# higheTemp.net
KiCad netlist of a schematic drawn in EAGLE
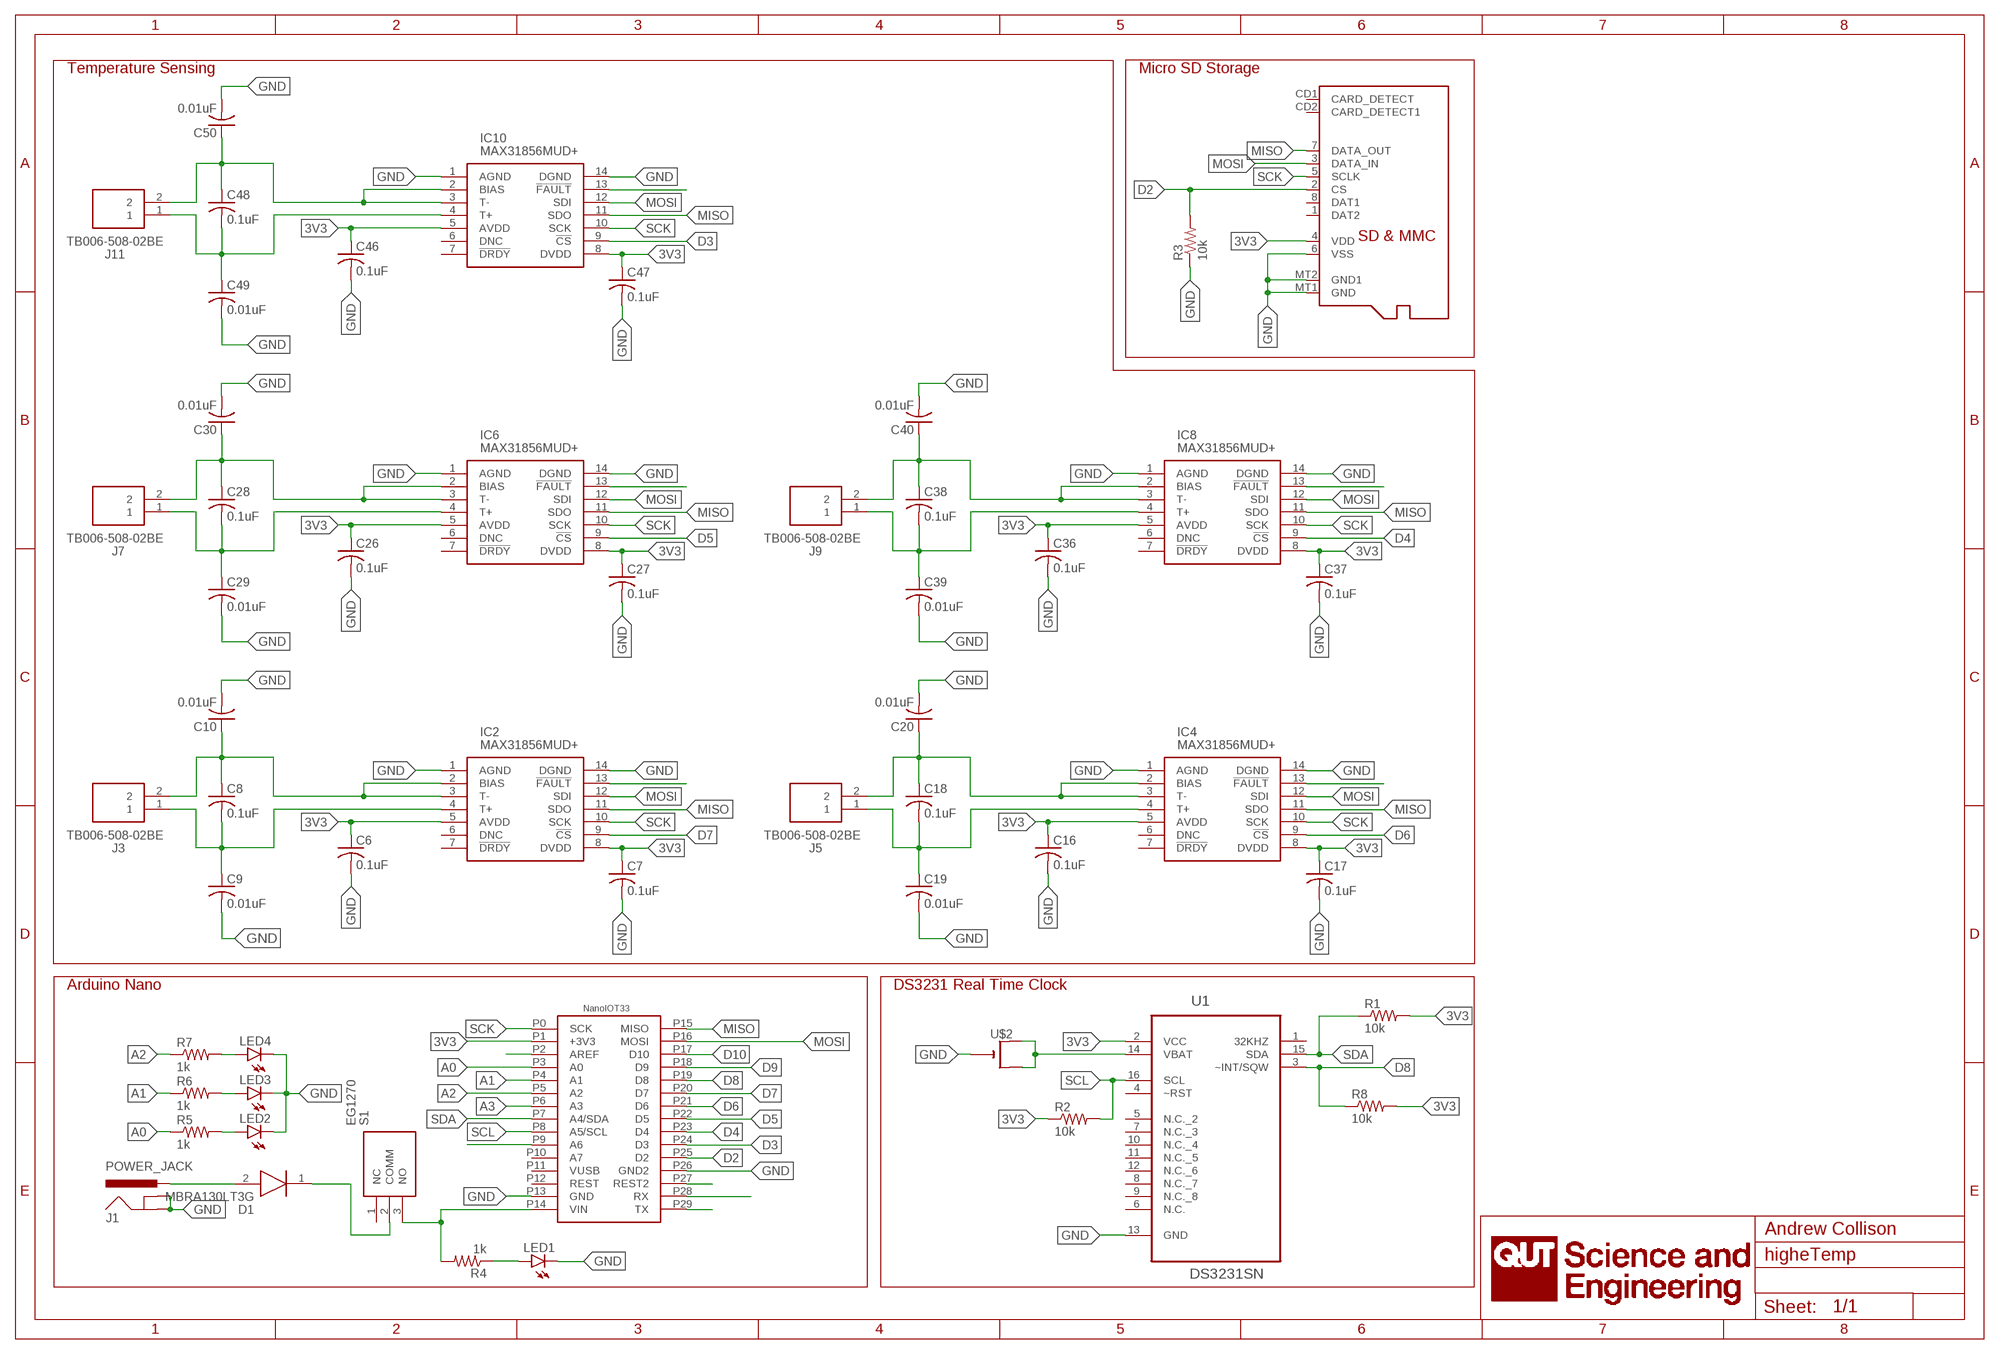
[diagram p0: schematic, sheet 1]

(export (version "E")
  (design (tool "Eeschema 10.0.6"))
  (components
    (comp (ref "C6")
      (value "0.1uF")
      (footprint "eagle-import:C0603")
      (libsource (lib "eagle-import") (part "C-USC0603"))
    )
    (comp (ref "C7")
      (value "0.1uF")
      (footprint "eagle-import:C0603")
      (libsource (lib "eagle-import") (part "C-USC0603"))
    )
    (comp (ref "C8")
      (value "0.1uF")
      (footprint "eagle-import:C0603")
      (libsource (lib "eagle-import") (part "C-USC0603"))
    )
    (comp (ref "C9")
      (value "0.01uF")
      (footprint "eagle-import:C0603")
      (libsource (lib "eagle-import") (part "C-USC0603"))
    )
    (comp (ref "C10")
      (value "0.01uF")
      (footprint "eagle-import:C0603")
      (libsource (lib "eagle-import") (part "C-USC0603"))
    )
    (comp (ref "C16")
      (value "0.1uF")
      (footprint "eagle-import:C0603")
      (libsource (lib "eagle-import") (part "C-USC0603"))
    )
    (comp (ref "C17")
      (value "0.1uF")
      (footprint "eagle-import:C0603")
      (libsource (lib "eagle-import") (part "C-USC0603"))
    )
    (comp (ref "C18")
      (value "0.1uF")
      (footprint "eagle-import:C0603")
      (libsource (lib "eagle-import") (part "C-USC0603"))
    )
    (comp (ref "C19")
      (value "0.01uF")
      (footprint "eagle-import:C0603")
      (libsource (lib "eagle-import") (part "C-USC0603"))
    )
    (comp (ref "C20")
      (value "0.01uF")
      (footprint "eagle-import:C0603")
      (libsource (lib "eagle-import") (part "C-USC0603"))
    )
    (comp (ref "C26")
      (value "0.1uF")
      (footprint "eagle-import:C0603")
      (libsource (lib "eagle-import") (part "C-USC0603"))
    )
    (comp (ref "C27")
      (value "0.1uF")
      (footprint "eagle-import:C0603")
      (libsource (lib "eagle-import") (part "C-USC0603"))
    )
    (comp (ref "C28")
      (value "0.1uF")
      (footprint "eagle-import:C0603")
      (libsource (lib "eagle-import") (part "C-USC0603"))
    )
    (comp (ref "C29")
      (value "0.01uF")
      (footprint "eagle-import:C0603")
      (libsource (lib "eagle-import") (part "C-USC0603"))
    )
    (comp (ref "C30")
      (value "0.01uF")
      (footprint "eagle-import:C0603")
      (libsource (lib "eagle-import") (part "C-USC0603"))
    )
    (comp (ref "C36")
      (value "0.1uF")
      (footprint "eagle-import:C0603")
      (libsource (lib "eagle-import") (part "C-USC0603"))
    )
    (comp (ref "C37")
      (value "0.1uF")
      (footprint "eagle-import:C0603")
      (libsource (lib "eagle-import") (part "C-USC0603"))
    )
    (comp (ref "C38")
      (value "0.1uF")
      (footprint "eagle-import:C0603")
      (libsource (lib "eagle-import") (part "C-USC0603"))
    )
    (comp (ref "C39")
      (value "0.01uF")
      (footprint "eagle-import:C0603")
      (libsource (lib "eagle-import") (part "C-USC0603"))
    )
    (comp (ref "C40")
      (value "0.01uF")
      (footprint "eagle-import:C0603")
      (libsource (lib "eagle-import") (part "C-USC0603"))
    )
    (comp (ref "C46")
      (value "0.1uF")
      (footprint "eagle-import:C0603")
      (libsource (lib "eagle-import") (part "C-USC0603"))
    )
    (comp (ref "C47")
      (value "0.1uF")
      (footprint "eagle-import:C0603")
      (libsource (lib "eagle-import") (part "C-USC0603"))
    )
    (comp (ref "C48")
      (value "0.1uF")
      (footprint "eagle-import:C0603")
      (libsource (lib "eagle-import") (part "C-USC0603"))
    )
    (comp (ref "C49")
      (value "0.01uF")
      (footprint "eagle-import:C0603")
      (libsource (lib "eagle-import") (part "C-USC0603"))
    )
    (comp (ref "C50")
      (value "0.01uF")
      (footprint "eagle-import:C0603")
      (libsource (lib "eagle-import") (part "C-USC0603"))
    )
    (comp (ref "D1")
      (value "MBRA130LT3G")
      (footprint "eagle-import:DIOM5226X220N")
      (fields (field (name "MOUSER_PART_NUMBER") "863-MBRA130LT3G"))
      (libsource (lib "eagle-import") (part "MBRA130LT3G"))
    )
    (comp (ref "IC2")
      (value "MAX31856MUD+")
      (footprint "eagle-import:SOP65P640X110-14N")
      (fields (field (name "MOUSER_PART_NUMBER") "700-MAX31856MUD+"))
      (libsource (lib "eagle-import") (part "MAX31856MUD+"))
    )
    (comp (ref "IC4")
      (value "MAX31856MUD+")
      (footprint "eagle-import:SOP65P640X110-14N")
      (fields (field (name "MOUSER_PART_NUMBER") "700-MAX31856MUD+"))
      (libsource (lib "eagle-import") (part "MAX31856MUD+"))
    )
    (comp (ref "IC6")
      (value "MAX31856MUD+")
      (footprint "eagle-import:SOP65P640X110-14N")
      (fields (field (name "MOUSER_PART_NUMBER") "700-MAX31856MUD+"))
      (libsource (lib "eagle-import") (part "MAX31856MUD+"))
    )
    (comp (ref "IC8")
      (value "MAX31856MUD+")
      (footprint "eagle-import:SOP65P640X110-14N")
      (fields (field (name "MOUSER_PART_NUMBER") "700-MAX31856MUD+"))
      (libsource (lib "eagle-import") (part "MAX31856MUD+"))
    )
    (comp (ref "IC10")
      (value "MAX31856MUD+")
      (footprint "eagle-import:SOP65P640X110-14N")
      (fields (field (name "MOUSER_PART_NUMBER") "700-MAX31856MUD+"))
      (libsource (lib "eagle-import") (part "MAX31856MUD+"))
    )
    (comp (ref "J1")
      (value "POWER_JACK")
      (footprint "eagle-import:POWER_JACK_PTH")
      (libsource (lib "eagle-import") (part "POWER_JACK"))
    )
    (comp (ref "J3")
      (value "TB006-508-02BE")
      (footprint "eagle-import:TB00650802BE")
      (fields (field (name "MOUSER_PART_NUMBER") "490-TB006-508-02BE"))
      (libsource (lib "eagle-import") (part "TB006-508-02BE"))
    )
    (comp (ref "J5")
      (value "TB006-508-02BE")
      (footprint "eagle-import:TB00650802BE")
      (fields (field (name "MOUSER_PART_NUMBER") "490-TB006-508-02BE"))
      (libsource (lib "eagle-import") (part "TB006-508-02BE"))
    )
    (comp (ref "J7")
      (value "TB006-508-02BE")
      (footprint "eagle-import:TB00650802BE")
      (fields (field (name "MOUSER_PART_NUMBER") "490-TB006-508-02BE"))
      (libsource (lib "eagle-import") (part "TB006-508-02BE"))
    )
    (comp (ref "J9")
      (value "TB006-508-02BE")
      (footprint "eagle-import:TB00650802BE")
      (fields (field (name "MOUSER_PART_NUMBER") "490-TB006-508-02BE"))
      (libsource (lib "eagle-import") (part "TB006-508-02BE"))
    )
    (comp (ref "J11")
      (value "TB006-508-02BE")
      (footprint "eagle-import:TB00650802BE")
      (fields (field (name "MOUSER_PART_NUMBER") "490-TB006-508-02BE"))
      (libsource (lib "eagle-import") (part "TB006-508-02BE"))
    )
    (comp (ref "LED1")
      (value "LEDCHIPLED_0805")
      (footprint "eagle-import:CHIPLED_0805")
      (libsource (lib "eagle-import") (part "LEDCHIPLED_0805"))
    )
    (comp (ref "LED2")
      (value "LEDCHIPLED_0805")
      (footprint "eagle-import:CHIPLED_0805")
      (libsource (lib "eagle-import") (part "LEDCHIPLED_0805"))
    )
    (comp (ref "LED3")
      (value "LEDCHIPLED_0805")
      (footprint "eagle-import:CHIPLED_0805")
      (libsource (lib "eagle-import") (part "LEDCHIPLED_0805"))
    )
    (comp (ref "LED4")
      (value "LEDCHIPLED_0805")
      (footprint "eagle-import:CHIPLED_0805")
      (libsource (lib "eagle-import") (part "LEDCHIPLED_0805"))
    )
    (comp (ref "R1")
      (value "10k")
      (footprint "eagle-import:R0603")
      (libsource (lib "eagle-import") (part "R-US_R0603"))
    )
    (comp (ref "R2")
      (value "10k")
      (footprint "eagle-import:R0603")
      (libsource (lib "eagle-import") (part "R-US_R0603"))
    )
    (comp (ref "R3")
      (value "10k")
      (footprint "eagle-import:R0805")
      (libsource (lib "eagle-import") (part "R-US_R0805"))
    )
    (comp (ref "R4")
      (value "1k")
      (footprint "eagle-import:R0603")
      (libsource (lib "eagle-import") (part "R-US_R0603"))
    )
    (comp (ref "R5")
      (value "1k")
      (footprint "eagle-import:R0603")
      (libsource (lib "eagle-import") (part "R-US_R0603"))
    )
    (comp (ref "R6")
      (value "1k")
      (footprint "eagle-import:R0603")
      (libsource (lib "eagle-import") (part "R-US_R0603"))
    )
    (comp (ref "R7")
      (value "1k")
      (footprint "eagle-import:R0603")
      (libsource (lib "eagle-import") (part "R-US_R0603"))
    )
    (comp (ref "R8")
      (value "10k")
      (footprint "eagle-import:R0805")
      (libsource (lib "eagle-import") (part "R-US_R0805"))
    )
    (comp (ref "S1")
      (value "EG1270")
      (footprint "eagle-import:EG1270")
      (fields (field (name "MOUSER_PART_NUMBER") "612-EG1270"))
      (libsource (lib "eagle-import") (part "EG1270"))
    )
    (comp (ref "U$1")
      (value "NANO33IOT")
      (footprint "eagle-import:NANO33IOT")
      (libsource (lib "eagle-import") (part "NANO33IOT"))
    )
    (comp (ref "U$2")
      (value "CR1220SMT")
      (footprint "eagle-import:CR1220-SMD")
      (libsource (lib "eagle-import") (part "CR1220SMT"))
    )
    (comp (ref "U$3")
      (value "MICROSD")
      (footprint "eagle-import:MICROSD")
      (libsource (lib "eagle-import") (part "MICROSD"))
    )
    (comp (ref "U1")
      (value "DS3231SN")
      (footprint "eagle-import:SOIC127P1032X265-16N")
      (fields (field (name "MPN") "DS3231SN#"))
      (libsource (lib "eagle-import") (part "DS3231SN"))
    )
  )
  (nets
    (net (code "1") (name "3V3") (class "Default")
      (node (ref "C16") (pin "1") (pinfunction "1_1") (pintype "passive"))
      (node (ref "C17") (pin "1") (pinfunction "1_1") (pintype "passive"))
      (node (ref "C26") (pin "1") (pinfunction "1_1") (pintype "passive"))
      (node (ref "C27") (pin "1") (pinfunction "1_1") (pintype "passive"))
      (node (ref "C36") (pin "1") (pinfunction "1_1") (pintype "passive"))
      (node (ref "C37") (pin "1") (pinfunction "1_1") (pintype "passive"))
      (node (ref "C46") (pin "1") (pinfunction "1_1") (pintype "passive"))
      (node (ref "C47") (pin "1") (pinfunction "1_1") (pintype "passive"))
      (node (ref "C6") (pin "1") (pinfunction "1_1") (pintype "passive"))
      (node (ref "C7") (pin "1") (pinfunction "1_1") (pintype "passive"))
      (node (ref "IC10") (pin "5") (pinfunction "AVDD_5") (pintype "power_in"))
      (node (ref "IC10") (pin "8") (pinfunction "DVDD_8") (pintype "power_in"))
      (node (ref "IC2") (pin "5") (pinfunction "AVDD_5") (pintype "power_in"))
      (node (ref "IC2") (pin "8") (pinfunction "DVDD_8") (pintype "power_in"))
      (node (ref "IC4") (pin "5") (pinfunction "AVDD_5") (pintype "power_in"))
      (node (ref "IC4") (pin "8") (pinfunction "DVDD_8") (pintype "power_in"))
      (node (ref "IC6") (pin "5") (pinfunction "AVDD_5") (pintype "power_in"))
      (node (ref "IC6") (pin "8") (pinfunction "DVDD_8") (pintype "power_in"))
      (node (ref "IC8") (pin "5") (pinfunction "AVDD_5") (pintype "power_in"))
      (node (ref "IC8") (pin "8") (pinfunction "DVDD_8") (pintype "power_in"))
      (node (ref "R1") (pin "2") (pinfunction "2_2") (pintype "passive"))
      (node (ref "R2") (pin "1") (pinfunction "1_1") (pintype "passive"))
      (node (ref "R8") (pin "2") (pinfunction "2_2") (pintype "passive"))
      (node (ref "U$1") (pin "P1") (pinfunction "+3V3_P1") (pintype "bidirectional"))
      (node (ref "U$3") (pin "4") (pinfunction "VDD_4") (pintype "power_in"))
      (node (ref "U1") (pin "2") (pinfunction "VCC_2") (pintype "power_in"))
    )
    (net (code "2") (name "A0") (class "Default")
      (node (ref "R5") (pin "1") (pinfunction "1_1") (pintype "passive"))
      (node (ref "U$1") (pin "P3") (pinfunction "A0_P3") (pintype "bidirectional"))
    )
    (net (code "3") (name "A1") (class "Default")
      (node (ref "R6") (pin "1") (pinfunction "1_1") (pintype "passive"))
      (node (ref "U$1") (pin "P4") (pinfunction "A1_P4") (pintype "bidirectional"))
    )
    (net (code "4") (name "A2") (class "Default")
      (node (ref "R7") (pin "1") (pinfunction "1_1") (pintype "passive"))
      (node (ref "U$1") (pin "P5") (pinfunction "A2_P5") (pintype "bidirectional"))
    )
    (net (code "5") (name "A3") (class "Default")
      (node (ref "U$1") (pin "P6") (pinfunction "A3_P6") (pintype "bidirectional"))
    )
    (net (code "6") (name "D2") (class "Default")
      (node (ref "R3") (pin "2") (pinfunction "2_2") (pintype "passive"))
      (node (ref "U$1") (pin "P25") (pinfunction "D2_P25") (pintype "bidirectional"))
      (node (ref "U$3") (pin "2") (pinfunction "CS_2") (pintype "input"))
    )
    (net (code "7") (name "D3") (class "Default")
      (node (ref "IC10") (pin "9") (pinfunction "~{CS}_9") (pintype "input"))
      (node (ref "U$1") (pin "P24") (pinfunction "D3_P24") (pintype "bidirectional"))
    )
    (net (code "8") (name "D4") (class "Default")
      (node (ref "IC8") (pin "9") (pinfunction "~{CS}_9") (pintype "input"))
      (node (ref "U$1") (pin "P23") (pinfunction "D4_P23") (pintype "bidirectional"))
    )
    (net (code "9") (name "D5") (class "Default")
      (node (ref "IC6") (pin "9") (pinfunction "~{CS}_9") (pintype "input"))
      (node (ref "U$1") (pin "P22") (pinfunction "D5_P22") (pintype "bidirectional"))
    )
    (net (code "10") (name "D6") (class "Default")
      (node (ref "IC4") (pin "9") (pinfunction "~{CS}_9") (pintype "input"))
      (node (ref "U$1") (pin "P21") (pinfunction "D6_P21") (pintype "bidirectional"))
    )
    (net (code "11") (name "D7") (class "Default")
      (node (ref "IC2") (pin "9") (pinfunction "~{CS}_9") (pintype "input"))
      (node (ref "U$1") (pin "P20") (pinfunction "D7_P20") (pintype "bidirectional"))
    )
    (net (code "12") (name "D8") (class "Default")
      (node (ref "R8") (pin "1") (pinfunction "1_1") (pintype "passive"))
      (node (ref "U$1") (pin "P19") (pinfunction "D8_P19") (pintype "bidirectional"))
      (node (ref "U1") (pin "3") (pinfunction "~{INT/SQW}_3") (pintype "output"))
    )
    (net (code "13") (name "D9") (class "Default")
      (node (ref "U$1") (pin "P18") (pinfunction "D9_P18") (pintype "bidirectional"))
    )
    (net (code "14") (name "D10") (class "Default")
      (node (ref "U$1") (pin "P17") (pinfunction "D10_P17") (pintype "bidirectional"))
    )
    (net (code "15") (name "GND") (class "Default")
      (node (ref "C10") (pin "2") (pinfunction "2_2") (pintype "passive"))
      (node (ref "C16") (pin "2") (pinfunction "2_2") (pintype "passive"))
      (node (ref "C17") (pin "2") (pinfunction "2_2") (pintype "passive"))
      (node (ref "C19") (pin "2") (pinfunction "2_2") (pintype "passive"))
      (node (ref "C20") (pin "2") (pinfunction "2_2") (pintype "passive"))
      (node (ref "C26") (pin "2") (pinfunction "2_2") (pintype "passive"))
      (node (ref "C27") (pin "2") (pinfunction "2_2") (pintype "passive"))
      (node (ref "C29") (pin "2") (pinfunction "2_2") (pintype "passive"))
      (node (ref "C30") (pin "2") (pinfunction "2_2") (pintype "passive"))
      (node (ref "C36") (pin "2") (pinfunction "2_2") (pintype "passive"))
      (node (ref "C37") (pin "2") (pinfunction "2_2") (pintype "passive"))
      (node (ref "C39") (pin "2") (pinfunction "2_2") (pintype "passive"))
      (node (ref "C40") (pin "2") (pinfunction "2_2") (pintype "passive"))
      (node (ref "C46") (pin "2") (pinfunction "2_2") (pintype "passive"))
      (node (ref "C47") (pin "2") (pinfunction "2_2") (pintype "passive"))
      (node (ref "C49") (pin "2") (pinfunction "2_2") (pintype "passive"))
      (node (ref "C50") (pin "2") (pinfunction "2_2") (pintype "passive"))
      (node (ref "C6") (pin "2") (pinfunction "2_2") (pintype "passive"))
      (node (ref "C7") (pin "2") (pinfunction "2_2") (pintype "passive"))
      (node (ref "C9") (pin "2") (pinfunction "2_2") (pintype "passive"))
      (node (ref "IC10") (pin "1") (pinfunction "AGND_1") (pintype "power_in"))
      (node (ref "IC10") (pin "14") (pinfunction "DGND_14") (pintype "power_in"))
      (node (ref "IC2") (pin "1") (pinfunction "AGND_1") (pintype "power_in"))
      (node (ref "IC2") (pin "14") (pinfunction "DGND_14") (pintype "power_in"))
      (node (ref "IC4") (pin "1") (pinfunction "AGND_1") (pintype "power_in"))
      (node (ref "IC4") (pin "14") (pinfunction "DGND_14") (pintype "power_in"))
      (node (ref "IC6") (pin "1") (pinfunction "AGND_1") (pintype "power_in"))
      (node (ref "IC6") (pin "14") (pinfunction "DGND_14") (pintype "power_in"))
      (node (ref "IC8") (pin "1") (pinfunction "AGND_1") (pintype "power_in"))
      (node (ref "IC8") (pin "14") (pinfunction "DGND_14") (pintype "power_in"))
      (node (ref "J1") (pin "GND") (pinfunction "GND_GND") (pintype "bidirectional"))
      (node (ref "J1") (pin "GNDBREAK") (pinfunction "GNDBREAK_GNDBREAK") (pintype "bidirectional"))
      (node (ref "LED1") (pin "C") (pinfunction "C_C") (pintype "passive"))
      (node (ref "LED2") (pin "C") (pinfunction "C_C") (pintype "passive"))
      (node (ref "LED3") (pin "C") (pinfunction "C_C") (pintype "passive"))
      (node (ref "LED4") (pin "C") (pinfunction "C_C") (pintype "passive"))
      (node (ref "R3") (pin "1") (pinfunction "1_1") (pintype "passive"))
      (node (ref "U$1") (pin "P13") (pinfunction "GND_P13") (pintype "bidirectional"))
      (node (ref "U$1") (pin "P26") (pinfunction "GND2_P26") (pintype "bidirectional"))
      (node (ref "U$2") (pin "-") (pinfunction "-_-") (pintype "passive"))
      (node (ref "U$3") (pin "6") (pinfunction "VSS_6") (pintype "power_in"))
      (node (ref "U$3") (pin "MT1") (pinfunction "GND_MT1") (pintype "power_in"))
      (node (ref "U$3") (pin "MT2") (pinfunction "GND1_MT2") (pintype "power_in"))
      (node (ref "U1") (pin "13") (pinfunction "GND_13") (pintype "passive"))
    )
    (net (code "16") (name "MISO") (class "Default")
      (node (ref "IC10") (pin "11") (pinfunction "SDO_11") (pintype "output"))
      (node (ref "IC2") (pin "11") (pinfunction "SDO_11") (pintype "output"))
      (node (ref "IC4") (pin "11") (pinfunction "SDO_11") (pintype "output"))
      (node (ref "IC6") (pin "11") (pinfunction "SDO_11") (pintype "output"))
      (node (ref "IC8") (pin "11") (pinfunction "SDO_11") (pintype "output"))
      (node (ref "U$1") (pin "P15") (pinfunction "MISO_P15") (pintype "bidirectional"))
      (node (ref "U$3") (pin "7") (pinfunction "DATA_OUT_7") (pintype "output"))
    )
    (net (code "17") (name "MOSI") (class "Default")
      (node (ref "IC10") (pin "12") (pinfunction "SDI_12") (pintype "input"))
      (node (ref "IC2") (pin "12") (pinfunction "SDI_12") (pintype "input"))
      (node (ref "IC4") (pin "12") (pinfunction "SDI_12") (pintype "input"))
      (node (ref "IC6") (pin "12") (pinfunction "SDI_12") (pintype "input"))
      (node (ref "IC8") (pin "12") (pinfunction "SDI_12") (pintype "input"))
      (node (ref "U$1") (pin "P16") (pinfunction "MOSI_P16") (pintype "bidirectional"))
      (node (ref "U$3") (pin "3") (pinfunction "DATA_IN_3") (pintype "input"))
    )
    (net (code "18") (name "Net-(D1-A)") (class "Default")
      (node (ref "D1") (pin "2") (pinfunction "A_2") (pintype "bidirectional"))
      (node (ref "J1") (pin "PWR") (pinfunction "PWR_PWR") (pintype "bidirectional"))
    )
    (net (code "19") (name "Net-(D1-K)") (class "Default")
      (node (ref "D1") (pin "1") (pinfunction "K_1") (pintype "bidirectional"))
      (node (ref "S1") (pin "2") (pinfunction "COMM_2") (pintype "bidirectional"))
    )
    (net (code "20") (name "Net-(IC2-BIAS)") (class "Default")
      (node (ref "C10") (pin "1") (pinfunction "1_1") (pintype "passive"))
      (node (ref "C8") (pin "1") (pinfunction "1_1") (pintype "passive"))
      (node (ref "IC2") (pin "2") (pinfunction "BIAS_2") (pintype "input"))
      (node (ref "IC2") (pin "3") (pinfunction "T-_3") (pintype "input"))
      (node (ref "J3") (pin "2") (pinfunction "2_2") (pintype "bidirectional"))
    )
    (net (code "21") (name "Net-(IC2-T+)") (class "Default")
      (node (ref "C8") (pin "2") (pinfunction "2_2") (pintype "passive"))
      (node (ref "C9") (pin "1") (pinfunction "1_1") (pintype "passive"))
      (node (ref "IC2") (pin "4") (pinfunction "T+_4") (pintype "input"))
      (node (ref "J3") (pin "1") (pinfunction "1_1") (pintype "bidirectional"))
    )
    (net (code "22") (name "Net-(IC4-BIAS)") (class "Default")
      (node (ref "C18") (pin "1") (pinfunction "1_1") (pintype "passive"))
      (node (ref "C20") (pin "1") (pinfunction "1_1") (pintype "passive"))
      (node (ref "IC4") (pin "2") (pinfunction "BIAS_2") (pintype "input"))
      (node (ref "IC4") (pin "3") (pinfunction "T-_3") (pintype "input"))
      (node (ref "J5") (pin "2") (pinfunction "2_2") (pintype "bidirectional"))
    )
    (net (code "23") (name "Net-(IC4-T+)") (class "Default")
      (node (ref "C18") (pin "2") (pinfunction "2_2") (pintype "passive"))
      (node (ref "C19") (pin "1") (pinfunction "1_1") (pintype "passive"))
      (node (ref "IC4") (pin "4") (pinfunction "T+_4") (pintype "input"))
      (node (ref "J5") (pin "1") (pinfunction "1_1") (pintype "bidirectional"))
    )
    (net (code "24") (name "Net-(IC6-BIAS)") (class "Default")
      (node (ref "C28") (pin "1") (pinfunction "1_1") (pintype "passive"))
      (node (ref "C30") (pin "1") (pinfunction "1_1") (pintype "passive"))
      (node (ref "IC6") (pin "2") (pinfunction "BIAS_2") (pintype "input"))
      (node (ref "IC6") (pin "3") (pinfunction "T-_3") (pintype "input"))
      (node (ref "J7") (pin "2") (pinfunction "2_2") (pintype "bidirectional"))
    )
    (net (code "25") (name "Net-(IC6-T+)") (class "Default")
      (node (ref "C28") (pin "2") (pinfunction "2_2") (pintype "passive"))
      (node (ref "C29") (pin "1") (pinfunction "1_1") (pintype "passive"))
      (node (ref "IC6") (pin "4") (pinfunction "T+_4") (pintype "input"))
      (node (ref "J7") (pin "1") (pinfunction "1_1") (pintype "bidirectional"))
    )
    (net (code "26") (name "Net-(IC8-BIAS)") (class "Default")
      (node (ref "C38") (pin "1") (pinfunction "1_1") (pintype "passive"))
      (node (ref "C40") (pin "1") (pinfunction "1_1") (pintype "passive"))
      (node (ref "IC8") (pin "2") (pinfunction "BIAS_2") (pintype "input"))
      (node (ref "IC8") (pin "3") (pinfunction "T-_3") (pintype "input"))
      (node (ref "J9") (pin "2") (pinfunction "2_2") (pintype "bidirectional"))
    )
    (net (code "27") (name "Net-(IC8-T+)") (class "Default")
      (node (ref "C38") (pin "2") (pinfunction "2_2") (pintype "passive"))
      (node (ref "C39") (pin "1") (pinfunction "1_1") (pintype "passive"))
      (node (ref "IC8") (pin "4") (pinfunction "T+_4") (pintype "input"))
      (node (ref "J9") (pin "1") (pinfunction "1_1") (pintype "bidirectional"))
    )
    (net (code "28") (name "Net-(IC10-BIAS)") (class "Default")
      (node (ref "C48") (pin "1") (pinfunction "1_1") (pintype "passive"))
      (node (ref "C50") (pin "1") (pinfunction "1_1") (pintype "passive"))
      (node (ref "IC10") (pin "2") (pinfunction "BIAS_2") (pintype "input"))
      (node (ref "IC10") (pin "3") (pinfunction "T-_3") (pintype "input"))
      (node (ref "J11") (pin "2") (pinfunction "2_2") (pintype "bidirectional"))
    )
    (net (code "29") (name "Net-(IC10-T+)") (class "Default")
      (node (ref "C48") (pin "2") (pinfunction "2_2") (pintype "passive"))
      (node (ref "C49") (pin "1") (pinfunction "1_1") (pintype "passive"))
      (node (ref "IC10") (pin "4") (pinfunction "T+_4") (pintype "input"))
      (node (ref "J11") (pin "1") (pinfunction "1_1") (pintype "bidirectional"))
    )
    (net (code "30") (name "Net-(LED1-PadA)") (class "Default")
      (node (ref "LED1") (pin "A") (pinfunction "A_A") (pintype "passive"))
      (node (ref "R4") (pin "1") (pinfunction "1_1") (pintype "passive"))
    )
    (net (code "31") (name "Net-(LED2-PadA)") (class "Default")
      (node (ref "LED2") (pin "A") (pinfunction "A_A") (pintype "passive"))
      (node (ref "R5") (pin "2") (pinfunction "2_2") (pintype "passive"))
    )
    (net (code "32") (name "Net-(LED3-PadA)") (class "Default")
      (node (ref "LED3") (pin "A") (pinfunction "A_A") (pintype "passive"))
      (node (ref "R6") (pin "2") (pinfunction "2_2") (pintype "passive"))
    )
    (net (code "33") (name "Net-(LED4-PadA)") (class "Default")
      (node (ref "LED4") (pin "A") (pinfunction "A_A") (pintype "passive"))
      (node (ref "R7") (pin "2") (pinfunction "2_2") (pintype "passive"))
    )
    (net (code "34") (name "Net-(S1-NO)") (class "Default")
      (node (ref "R4") (pin "2") (pinfunction "2_2") (pintype "passive"))
      (node (ref "S1") (pin "3") (pinfunction "NO_3") (pintype "bidirectional"))
      (node (ref "U$1") (pin "P14") (pinfunction "VIN_P14") (pintype "bidirectional"))
    )
    (net (code "35") (name "Net-(U$2-+)") (class "Default")
      (node (ref "U$2") (pin "+$1") (pinfunction "+_+$1") (pintype "passive"))
      (node (ref "U$2") (pin "+$2") (pinfunction "+1_+$2") (pintype "passive"))
      (node (ref "U1") (pin "14") (pinfunction "VBAT_14") (pintype "power_in"))
    )
    (net (code "36") (name "SCK") (class "Default")
      (node (ref "IC10") (pin "10") (pinfunction "SCK_10") (pintype "input"))
      (node (ref "IC2") (pin "10") (pinfunction "SCK_10") (pintype "input"))
      (node (ref "IC4") (pin "10") (pinfunction "SCK_10") (pintype "input"))
      (node (ref "IC6") (pin "10") (pinfunction "SCK_10") (pintype "input"))
      (node (ref "IC8") (pin "10") (pinfunction "SCK_10") (pintype "input"))
      (node (ref "U$1") (pin "P0") (pinfunction "SCK_P0") (pintype "bidirectional"))
      (node (ref "U$3") (pin "5") (pinfunction "SCLK_5") (pintype "input"))
    )
    (net (code "37") (name "SCL") (class "Default")
      (node (ref "R2") (pin "2") (pinfunction "2_2") (pintype "passive"))
      (node (ref "U$1") (pin "P8") (pinfunction "A5/SCL_P8") (pintype "bidirectional"))
      (node (ref "U1") (pin "16") (pinfunction "SCL_16") (pintype "input"))
    )
    (net (code "38") (name "SDA") (class "Default")
      (node (ref "R1") (pin "1") (pinfunction "1_1") (pintype "passive"))
      (node (ref "U$1") (pin "P7") (pinfunction "A4/SDA_P7") (pintype "bidirectional"))
      (node (ref "U1") (pin "15") (pinfunction "SDA_15") (pintype "bidirectional"))
    )
    (net (code "39") (name "unconnected-(IC2-DNC-Pad6)") (class "Default")
      (node (ref "IC2") (pin "6") (pinfunction "DNC_6") (pintype "bidirectional"))
    )
    (net (code "40") (name "unconnected-(IC2-~{DRDY}-Pad7)") (class "Default")
      (node (ref "IC2") (pin "7") (pinfunction "~{DRDY}_7") (pintype "output"))
    )
    (net (code "41") (name "unconnected-(IC2-~{FAULT}-Pad13)") (class "Default")
      (node (ref "IC2") (pin "13") (pinfunction "~{FAULT}_13") (pintype "output"))
    )
    (net (code "42") (name "unconnected-(IC4-DNC-Pad6)") (class "Default")
      (node (ref "IC4") (pin "6") (pinfunction "DNC_6") (pintype "bidirectional"))
    )
    (net (code "43") (name "unconnected-(IC4-~{DRDY}-Pad7)") (class "Default")
      (node (ref "IC4") (pin "7") (pinfunction "~{DRDY}_7") (pintype "output"))
    )
    (net (code "44") (name "unconnected-(IC4-~{FAULT}-Pad13)") (class "Default")
      (node (ref "IC4") (pin "13") (pinfunction "~{FAULT}_13") (pintype "output"))
    )
    (net (code "45") (name "unconnected-(IC6-DNC-Pad6)") (class "Default")
      (node (ref "IC6") (pin "6") (pinfunction "DNC_6") (pintype "bidirectional"))
    )
    (net (code "46") (name "unconnected-(IC6-~{DRDY}-Pad7)") (class "Default")
      (node (ref "IC6") (pin "7") (pinfunction "~{DRDY}_7") (pintype "output"))
    )
    (net (code "47") (name "unconnected-(IC6-~{FAULT}-Pad13)") (class "Default")
      (node (ref "IC6") (pin "13") (pinfunction "~{FAULT}_13") (pintype "output"))
    )
    (net (code "48") (name "unconnected-(IC8-DNC-Pad6)") (class "Default")
      (node (ref "IC8") (pin "6") (pinfunction "DNC_6") (pintype "bidirectional"))
    )
    (net (code "49") (name "unconnected-(IC8-~{DRDY}-Pad7)") (class "Default")
      (node (ref "IC8") (pin "7") (pinfunction "~{DRDY}_7") (pintype "output"))
    )
    (net (code "50") (name "unconnected-(IC8-~{FAULT}-Pad13)") (class "Default")
      (node (ref "IC8") (pin "13") (pinfunction "~{FAULT}_13") (pintype "output"))
    )
    (net (code "51") (name "unconnected-(IC10-DNC-Pad6)") (class "Default")
      (node (ref "IC10") (pin "6") (pinfunction "DNC_6") (pintype "bidirectional"))
    )
    (net (code "52") (name "unconnected-(IC10-~{DRDY}-Pad7)") (class "Default")
      (node (ref "IC10") (pin "7") (pinfunction "~{DRDY}_7") (pintype "output"))
    )
    (net (code "53") (name "unconnected-(IC10-~{FAULT}-Pad13)") (class "Default")
      (node (ref "IC10") (pin "13") (pinfunction "~{FAULT}_13") (pintype "output"))
    )
    (net (code "54") (name "unconnected-(S1-NC-Pad1)") (class "Default")
      (node (ref "S1") (pin "1") (pinfunction "NC_1") (pintype "no_connect"))
    )
    (net (code "55") (name "unconnected-(U$1-A6-PadP9)") (class "Default")
      (node (ref "U$1") (pin "P9") (pinfunction "A6_P9") (pintype "bidirectional"))
    )
    (net (code "56") (name "unconnected-(U$1-A7-PadP10)") (class "Default")
      (node (ref "U$1") (pin "P10") (pinfunction "A7_P10") (pintype "bidirectional"))
    )
    (net (code "57") (name "unconnected-(U$1-AREF-PadP2)") (class "Default")
      (node (ref "U$1") (pin "P2") (pinfunction "AREF_P2") (pintype "bidirectional"))
    )
    (net (code "58") (name "unconnected-(U$1-REST-PadP12)") (class "Default")
      (node (ref "U$1") (pin "P12") (pinfunction "REST_P12") (pintype "bidirectional"))
    )
    (net (code "59") (name "unconnected-(U$1-REST2-PadP27)") (class "Default")
      (node (ref "U$1") (pin "P27") (pinfunction "REST2_P27") (pintype "bidirectional"))
    )
    (net (code "60") (name "unconnected-(U$1-RX-PadP28)") (class "Default")
      (node (ref "U$1") (pin "P28") (pinfunction "RX_P28") (pintype "bidirectional"))
    )
    (net (code "61") (name "unconnected-(U$1-TX-PadP29)") (class "Default")
      (node (ref "U$1") (pin "P29") (pinfunction "TX_P29") (pintype "bidirectional"))
    )
    (net (code "62") (name "unconnected-(U$1-VUSB-PadP11)") (class "Default")
      (node (ref "U$1") (pin "P11") (pinfunction "VUSB_P11") (pintype "bidirectional"))
    )
    (net (code "63") (name "unconnected-(U$3-CARD_DETECT-PadCD1)") (class "Default")
      (node (ref "U$3") (pin "CD1") (pinfunction "CARD_DETECT_CD1") (pintype "passive"))
    )
    (net (code "64") (name "unconnected-(U$3-CARD_DETECT1-PadCD2)") (class "Default")
      (node (ref "U$3") (pin "CD2") (pinfunction "CARD_DETECT1_CD2") (pintype "passive"))
    )
    (net (code "65") (name "unconnected-(U$3-DAT1-Pad8)") (class "Default")
      (node (ref "U$3") (pin "8") (pinfunction "DAT1_8") (pintype "bidirectional"))
    )
    (net (code "66") (name "unconnected-(U$3-DAT2-Pad1)") (class "Default")
      (node (ref "U$3") (pin "1") (pinfunction "DAT2_1") (pintype "bidirectional"))
    )
    (net (code "67") (name "unconnected-(U1-32KHZ-Pad1)") (class "Default")
      (node (ref "U1") (pin "1") (pinfunction "32KHZ_1") (pintype "output"))
    )
    (net (code "68") (name "unconnected-(U1-N.C.-Pad6)") (class "Default")
      (node (ref "U1") (pin "6") (pinfunction "N.C._6") (pintype "no_connect"))
    )
    (net (code "69") (name "unconnected-(U1-N.C._2-Pad5)") (class "Default")
      (node (ref "U1") (pin "5") (pinfunction "N.C._2_5") (pintype "no_connect"))
    )
    (net (code "70") (name "unconnected-(U1-N.C._3-Pad7)") (class "Default")
      (node (ref "U1") (pin "7") (pinfunction "N.C._3_7") (pintype "no_connect"))
    )
    (net (code "71") (name "unconnected-(U1-N.C._4-Pad10)") (class "Default")
      (node (ref "U1") (pin "10") (pinfunction "N.C._4_10") (pintype "no_connect"))
    )
    (net (code "72") (name "unconnected-(U1-N.C._5-Pad11)") (class "Default")
      (node (ref "U1") (pin "11") (pinfunction "N.C._5_11") (pintype "no_connect"))
    )
    (net (code "73") (name "unconnected-(U1-N.C._6-Pad12)") (class "Default")
      (node (ref "U1") (pin "12") (pinfunction "N.C._6_12") (pintype "no_connect"))
    )
    (net (code "74") (name "unconnected-(U1-N.C._7-Pad8)") (class "Default")
      (node (ref "U1") (pin "8") (pinfunction "N.C._7_8") (pintype "no_connect"))
    )
    (net (code "75") (name "unconnected-(U1-N.C._8-Pad9)") (class "Default")
      (node (ref "U1") (pin "9") (pinfunction "N.C._8_9") (pintype "no_connect"))
    )
    (net (code "76") (name "unconnected-(U1-~{RST}-Pad4)") (class "Default")
      (node (ref "U1") (pin "4") (pinfunction "~{RST}_4") (pintype "bidirectional"))
    )
  )
)
